# Humi_Light_Pump.net
KiCad netlist of a schematic drawn in Altium Designer
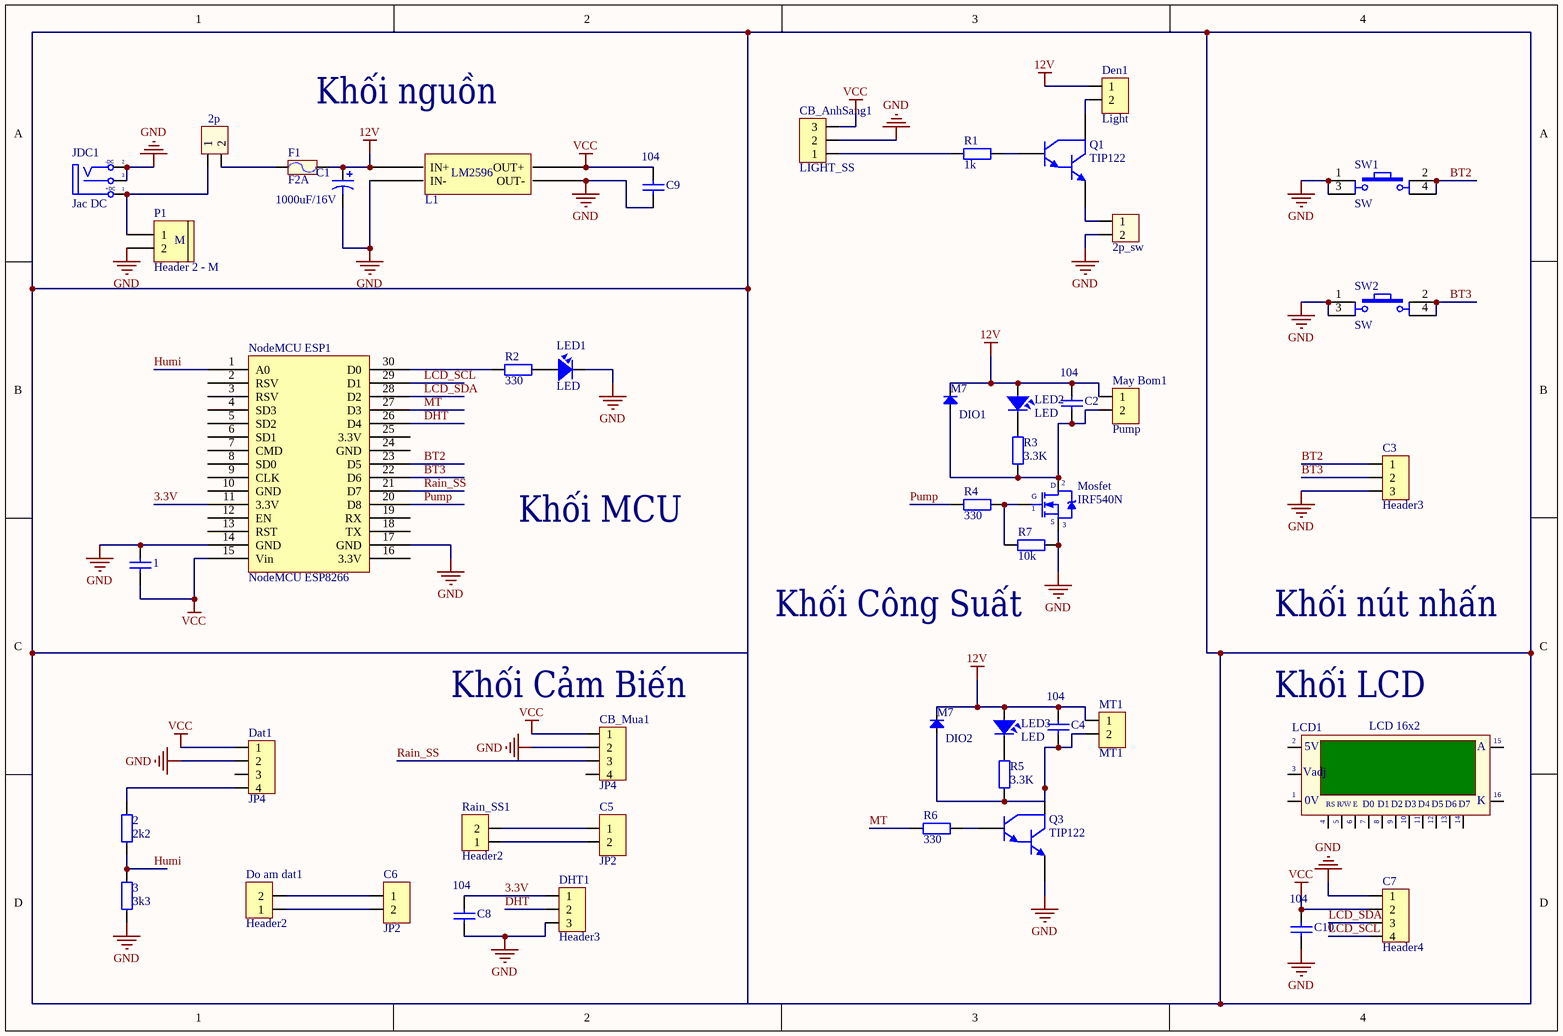
[diagram p0: Humi_Light_Pump.SchDoc]

(export (version "E")
  (design (tool "Eeschema 10.0.6"))
  (components
    (comp (ref "1")
      (value "Capacitor Ceramic")
      (footprint "C1206")
      (description "Capacitor")
      (fields (field (name "PUBLISHER") "Altium Limited"))
      (libsource (lib "My Library") (part "CapSMD"))
    )
    (comp (ref "2")
      (value "2k2")
      (footprint "RES-SMD-1206")
      (description "Resistor SMD 0805")
      (fields (field (name "PUBLISHER") "Altium Limited"))
      (libsource (lib "") (part "R0805_1"))
    )
    (comp (ref "3")
      (value "3k3")
      (footprint "RES-SMD-1206")
      (description "Resistor SMD 0805")
      (fields (field (name "PUBLISHER") "Altium Limited"))
      (libsource (lib "") (part "R0805_1"))
    )
    (comp (ref "C1")
      (value "1000uF/16V")
      (footprint "C8mm")
      (description "Polarized Capacitor (Axial)")
      (fields (field (name "PUBLISHER") "Altium Limited"))
      (libsource (lib "My Library") (part "Cap Pol 12mm"))
    )
    (comp (ref "C2")
      (value "104")
      (footprint "C1206")
      (description "Capacitor")
      (fields (field (name "PUBLISHER") "Altium Limited"))
      (libsource (lib "My Library") (part "CapSMD"))
    )
    (comp (ref "C3")
      (value "Header3")
      (footprint "Header3")
      (description "Header IDC, 3 x 1 Pin Vertical 2.54mm Pitch (Non-Boxed, Male)")
      (fields
        (field (name "MANUFACTURER") "Würth Elektronik eiSos GmbH")
        (field (name "PARTNO") "613002143121")
        (field (name "CREATED BY") "Karrer Zheng")
      )
      (libsource (lib "My Library") (part "Header3"))
    )
    (comp (ref "C4")
      (value "104")
      (footprint "C1206")
      (description "Capacitor")
      (fields (field (name "PUBLISHER") "Altium Limited"))
      (libsource (lib "My Library") (part "CapSMD"))
    )
    (comp (ref "C5")
      (value "JP2")
      (footprint "Header 2P DC 2.54")
      (description "WR-PHD 2.54 mm Angled Socket Header")
      (fields
        (field (name "MANUFACTURER") "Würth Elektronik eiSos GmbH")
        (field (name "PARTNO") "613002143121")
        (field (name "CREATED BY") "Karrer Zheng")
      )
      (libsource (lib "My Library") (part "JP2"))
    )
    (comp (ref "C6")
      (value "JP2")
      (footprint "Header 2P DC 2.54")
      (description "WR-PHD 2.54 mm Angled Socket Header")
      (fields
        (field (name "MANUFACTURER") "Würth Elektronik eiSos GmbH")
        (field (name "PARTNO") "613002143121")
        (field (name "CREATED BY") "Karrer Zheng")
      )
      (libsource (lib "My Library") (part "JP2"))
    )
    (comp (ref "C7")
      (value "Header4")
      (footprint "XH2.54M-4")
      (description "Header IDC, 4 x 1 Pin Vertical 2.54mm Pitch (Non-Boxed, Male)")
      (fields
        (field (name "MANUFACTURER") "Würth Elektronik eiSos GmbH")
        (field (name "PARTNO") "613002143121")
        (field (name "CREATED BY") "Karrer Zheng")
      )
      (libsource (lib "My Library") (part "Header4"))
    )
    (comp (ref "C8")
      (value "104")
      (footprint "C1206")
      (description "Capacitor")
      (fields (field (name "PUBLISHER") "Altium Limited"))
      (libsource (lib "My Library") (part "CapSMD"))
    )
    (comp (ref "C9")
      (value "104")
      (footprint "C1206")
      (description "Capacitor")
      (fields (field (name "PUBLISHER") "Altium Limited"))
      (libsource (lib "My Library") (part "CapSMD"))
    )
    (comp (ref "C10")
      (value "104")
      (footprint "C1206")
      (description "Capacitor")
      (fields (field (name "PUBLISHER") "Altium Limited"))
      (libsource (lib "My Library") (part "CapSMD"))
    )
    (comp (ref "CB_AnhSang1")
      (value "LIGHT_SS")
      (footprint "Header 3P DC 2.54")
      (description "Header IDC, 3 x 1 Pin Vertical 2.54mm Pitch (Non-Boxed, Male)")
      (fields
        (field (name "MANUFACTURER") "Würth Elektronik eiSos GmbH")
        (field (name "PARTNO") "613002143121")
        (field (name "CREATED BY") "Karrer Zheng")
      )
      (libsource (lib "") (part "Header3_1"))
    )
    (comp (ref "CB_Mua1")
      (value "JP4")
      (footprint "JP4-C1T")
      (description "Header IDC, 4 x 1 Pin Vertical 2.54mm Pitch (Non-Boxed, Male)")
      (fields
        (field (name "MANUFACTURER") "Würth Elektronik eiSos GmbH")
        (field (name "PARTNO") "613002143121")
        (field (name "CREATED BY") "Karrer Zheng")
      )
      (libsource (lib "My Library") (part "Header4"))
    )
    (comp (ref "Dat1")
      (value "JP4")
      (footprint "JP4-C1T")
      (description "Header IDC, 4 x 1 Pin Vertical 2.54mm Pitch (Non-Boxed, Male)")
      (fields
        (field (name "MANUFACTURER") "Würth Elektronik eiSos GmbH")
        (field (name "PARTNO") "613002143121")
        (field (name "CREATED BY") "Karrer Zheng")
      )
      (libsource (lib "My Library") (part "Header4"))
    )
    (comp (ref "Den1")
      (value "Light")
      (footprint "Header 2P DC 2.54")
      (description "Header IDC, 2 x 1 Pin Vertical 2.54mm Pitch (Non-Boxed, Male)")
      (fields
        (field (name "MANUFACTURER") "Würth Elektronik eiSos GmbH")
        (field (name "PARTNO") "613002143121")
        (field (name "CREATED BY") "Karrer Zheng")
      )
      (libsource (lib "My Library") (part "Header2"))
    )
    (comp (ref "DHT1")
      (value "Header3")
      (footprint "Header 3P DC 2.54")
      (description "Header IDC, 3 x 1 Pin Vertical 2.54mm Pitch (Non-Boxed, Male)")
      (fields
        (field (name "MANUFACTURER") "Würth Elektronik eiSos GmbH")
        (field (name "PARTNO") "613002143121")
        (field (name "CREATED BY") "Karrer Zheng")
      )
      (libsource (lib "My Library") (part "Header3"))
    )
    (comp (ref "DIO1")
      (value "M7")
      (footprint "DIO-SMD-106")
      (description "Default Diode")
      (fields (field (name "PUBLISHER") "Altium Limited"))
      (libsource (lib "My Library (1)") (part "Diode SMD"))
    )
    (comp (ref "DIO2")
      (value "M7")
      (footprint "DIO-SMD-106")
      (description "Default Diode")
      (fields (field (name "PUBLISHER") "Altium Limited"))
      (libsource (lib "My Library (1)") (part "Diode SMD"))
    )
    (comp (ref "Do am dat1")
      (value "Header2")
      (footprint "Header2")
      (description "Header IDC, 2 x 1 Pin Vertical 2.54mm Pitch (Non-Boxed, Male)")
      (fields
        (field (name "MANUFACTURER") "Würth Elektronik eiSos GmbH")
        (field (name "PARTNO") "613002143121")
        (field (name "CREATED BY") "Karrer Zheng")
      )
      (libsource (lib "") (part "Header2_1"))
    )
    (comp (ref "F1")
      (value "F2A")
      (footprint "Fuse")
      (description "Fuse")
      (fields (field (name "DESIGNED BY") "VanDungEvn"))
      (libsource (lib "My Library") (part "Fuse"))
    )
    (comp (ref "H1")
      (value "2p")
      (footprint "XH2.54M-2")
      (description "Cắm")
      (libsource (lib "") (part "Header 2P 2.54 Duc Thang_1"))
    )
    (comp (ref "H2")
      (value "2p_sw")
      (footprint "XH2.54M-2")
      (description "Cắm")
      (libsource (lib "Header") (part "Header 2P 2.54 Duc Thang"))
    )
    (comp (ref "JDC1")
      (value "Jac DC")
      (footprint "DC-IN")
      (description "Jac DC input")
      (libsource (lib "My Library") (part "DCIN"))
    )
    (comp (ref "L1")
      (value "BUCK_LM2596")
      (footprint "BUCK_LM2596")
      (libsource (lib "BUCK_LM2596_Sch") (part "BUCK_LM2596"))
    )
    (comp (ref "LCD1")
      (value "LCD 16x2")
      (footprint "LCD16X2N")
      (libsource (lib "My library altium") (part "LCD"))
    )
    (comp (ref "LED1")
      (value "LED")
      (footprint "LED-5 GRe")
      (description "LED Single colour Green and Red")
      (libsource (lib "My Library") (part "LED"))
    )
    (comp (ref "LED2")
      (value "LED")
      (footprint "LED-5 GRe")
      (description "LED Single colour Green and Red")
      (libsource (lib "My Library") (part "LED"))
    )
    (comp (ref "LED3")
      (value "LED")
      (footprint "LED-5 GRe")
      (description "LED Single colour Green and Red")
      (libsource (lib "My Library") (part "LED"))
    )
    (comp (ref "May Bom1")
      (value "Pump")
      (footprint "Header 2P DC 2.54")
      (description "Header IDC, 2 x 1 Pin Vertical 2.54mm Pitch (Non-Boxed, Male)")
      (fields
        (field (name "MANUFACTURER") "Würth Elektronik eiSos GmbH")
        (field (name "PARTNO") "613002143121")
        (field (name "CREATED BY") "Karrer Zheng")
      )
      (libsource (lib "My Library") (part "Header2"))
    )
    (comp (ref "Mosfet")
      (value "IRF540N")
      (footprint "QTO-220")
      (description "MOSFET N - CHANNEL 500V - 0.75 - 8A - TO-220")
      (libsource (lib "My Library") (part "IRF840"))
    )
    (comp (ref "MT1")
      (value "MT1")
      (footprint "Header 2P DC 2.54")
      (description "Header IDC, 2 x 1 Pin Vertical 2.54mm Pitch (Non-Boxed, Male)")
      (fields
        (field (name "MANUFACTURER") "Würth Elektronik eiSos GmbH")
        (field (name "PARTNO") "613002143121")
        (field (name "CREATED BY") "Karrer Zheng")
      )
      (libsource (lib "My Library") (part "Header2"))
    )
    (comp (ref "NodeMCU ESP1")
      (value "NodeMCU ESP8266")
      (footprint "NodeMCU ESP8266")
      (libsource (lib "Phieu_Du") (part "NodeMCU ESP8266"))
    )
    (comp (ref "P1")
      (value "Header 2 - M")
      (footprint "Medium - Header 2")
      (description "Header, 2-Pin, Medium")
      (fields (field (name "PUBLISHER") "Altium Limited"))
      (libsource (lib "My Library") (part "Header 2 - M"))
    )
    (comp (ref "Q1")
      (value "TIP122")
      (footprint "QTO-220")
      (description "Darlington Silicon Power NPN Transistor, 8 Amp, 100 Volts and 65 Watts")
      (libsource (lib "My Library (1)") (part "TIP122"))
    )
    (comp (ref "Q3")
      (value "TIP122")
      (footprint "QTO-220")
      (description "Darlington Silicon Power NPN Transistor, 8 Amp, 100 Volts and 65 Watts")
      (libsource (lib "My Library (1)") (part "TIP122"))
    )
    (comp (ref "R1")
      (value "1k")
      (footprint "RES-SMD-1206")
      (description "Resistor SMD 0805")
      (fields (field (name "PUBLISHER") "Altium Limited"))
      (libsource (lib "My Library (1)") (part "R0805"))
    )
    (comp (ref "R2")
      (value "330")
      (footprint "RES-SMD-1206")
      (description "Resistor SMD 0805")
      (fields (field (name "PUBLISHER") "Altium Limited"))
      (libsource (lib "My Library (1)") (part "R0805"))
    )
    (comp (ref "R3")
      (value "3.3K")
      (footprint "RES-SMD-1206")
      (description "Resistor SMD 0805")
      (fields (field (name "PUBLISHER") "Altium Limited"))
      (libsource (lib "") (part "R0805_1"))
    )
    (comp (ref "R4")
      (value "330")
      (footprint "RES-SMD-1206")
      (description "Resistor SMD 0805")
      (fields (field (name "PUBLISHER") "Altium Limited"))
      (libsource (lib "My Library (1)") (part "R0805"))
    )
    (comp (ref "R5")
      (value "3.3K")
      (footprint "RES-SMD-1206")
      (description "Resistor SMD 0805")
      (fields (field (name "PUBLISHER") "Altium Limited"))
      (libsource (lib "") (part "R0805_1"))
    )
    (comp (ref "R6")
      (value "330")
      (footprint "RES-SMD-1206")
      (description "Resistor SMD 0805")
      (fields (field (name "PUBLISHER") "Altium Limited"))
      (libsource (lib "My Library (1)") (part "R0805"))
    )
    (comp (ref "R7")
      (value "10k")
      (footprint "RES-SMD-1206")
      (description "Resistor SMD 0805")
      (fields (field (name "PUBLISHER") "Altium Limited"))
      (libsource (lib "My Library (1)") (part "R0805"))
    )
    (comp (ref "Rain_SS1")
      (value "Header2")
      (footprint "Header2")
      (description "Header IDC, 2 x 1 Pin Vertical 2.54mm Pitch (Non-Boxed, Male)")
      (fields
        (field (name "MANUFACTURER") "Würth Elektronik eiSos GmbH")
        (field (name "PARTNO") "613002143121")
        (field (name "CREATED BY") "Karrer Zheng")
      )
      (libsource (lib "") (part "Header2_1"))
    )
    (comp (ref "SW1")
      (value "SW")
      (footprint "SW4")
      (description "Switch button 4 pin")
      (libsource (lib "My Library (1)") (part "SW4"))
    )
    (comp (ref "SW2")
      (value "SW")
      (footprint "SW4")
      (description "Switch button 4 pin")
      (libsource (lib "My Library (1)") (part "SW4"))
    )
  )
  (nets
    (net (code "1") (name "/3.3V") (class "Default")
      (node (ref "C8") (pin "2") (pinfunction "2_2") (pintype "passive"))
      (node (ref "DHT1") (pin "1") (pinfunction "1_1") (pintype "passive"))
      (node (ref "NodeMCU ESP1") (pin "11") (pinfunction "3.3V_11") (pintype "passive"))
    )
    (net (code "2") (name "/BT2") (class "Default")
      (node (ref "C3") (pin "1") (pinfunction "1_1") (pintype "passive"))
      (node (ref "NodeMCU ESP1") (pin "23") (pinfunction "D5_23") (pintype "passive"))
      (node (ref "SW1") (pin "2") (pintype "passive"))
      (node (ref "SW1") (pin "4") (pintype "passive"))
    )
    (net (code "3") (name "/BT3") (class "Default")
      (node (ref "C3") (pin "2") (pinfunction "2_2") (pintype "passive"))
      (node (ref "NodeMCU ESP1") (pin "22") (pinfunction "D6_22") (pintype "passive"))
      (node (ref "SW2") (pin "2") (pintype "passive"))
      (node (ref "SW2") (pin "4") (pintype "passive"))
    )
    (net (code "4") (name "/DHT") (class "Default")
      (node (ref "DHT1") (pin "2") (pinfunction "2_2") (pintype "passive"))
      (node (ref "NodeMCU ESP1") (pin "26") (pinfunction "D4_26") (pintype "passive"))
    )
    (net (code "5") (name "/Humi") (class "Default")
      (node (ref "2") (pin "2") (pinfunction "2_2") (pintype "passive"))
      (node (ref "3") (pin "1") (pinfunction "1_1") (pintype "passive"))
      (node (ref "NodeMCU ESP1") (pin "1") (pinfunction "A0_1") (pintype "passive"))
    )
    (net (code "6") (name "/LCD_SCL") (class "Default")
      (node (ref "C7") (pin "4") (pinfunction "4_4") (pintype "passive"))
      (node (ref "NodeMCU ESP1") (pin "29") (pinfunction "D1_29") (pintype "passive"))
    )
    (net (code "7") (name "/LCD_SDA") (class "Default")
      (node (ref "C7") (pin "3") (pinfunction "3_3") (pintype "passive"))
      (node (ref "NodeMCU ESP1") (pin "28") (pinfunction "D2_28") (pintype "passive"))
    )
    (net (code "8") (name "/MT") (class "Default")
      (node (ref "NodeMCU ESP1") (pin "27") (pinfunction "D3_27") (pintype "passive"))
      (node (ref "R6") (pin "2") (pinfunction "2_2") (pintype "passive"))
    )
    (net (code "9") (name "/Pump") (class "Default")
      (node (ref "NodeMCU ESP1") (pin "20") (pinfunction "D8_20") (pintype "passive"))
      (node (ref "R4") (pin "2") (pinfunction "2_2") (pintype "passive"))
    )
    (net (code "10") (name "/Rain_SS") (class "Default")
      (node (ref "CB_Mua1") (pin "3") (pinfunction "3_3") (pintype "passive"))
      (node (ref "NodeMCU ESP1") (pin "21") (pinfunction "D7_21") (pintype "passive"))
    )
    (net (code "11") (name "12V") (class "Default")
      (node (ref "C1") (pin "1") (pinfunction "1_1") (pintype "passive"))
      (node (ref "C2") (pin "2") (pinfunction "2_2") (pintype "passive"))
      (node (ref "C4") (pin "2") (pinfunction "2_2") (pintype "passive"))
      (node (ref "DIO1") (pin "2") (pinfunction "K_2") (pintype "passive"))
      (node (ref "DIO2") (pin "2") (pinfunction "K_2") (pintype "passive"))
      (node (ref "Den1") (pin "1") (pinfunction "1_1") (pintype "passive"))
      (node (ref "F1") (pin "2") (pinfunction "2_2") (pintype "passive"))
      (node (ref "L1") (pin "1") (pinfunction "IN+_1") (pintype "passive"))
      (node (ref "LED2") (pin "1") (pinfunction "1_1") (pintype "passive"))
      (node (ref "LED3") (pin "1") (pinfunction "1_1") (pintype "passive"))
      (node (ref "MT1") (pin "1") (pinfunction "1_1") (pintype "passive"))
      (node (ref "May Bom1") (pin "1") (pinfunction "1_1") (pintype "passive"))
    )
    (net (code "12") (name "GND") (class "Default")
      (node (ref "1") (pin "2") (pinfunction "2_2") (pintype "passive"))
      (node (ref "3") (pin "2") (pinfunction "2_2") (pintype "passive"))
      (node (ref "C1") (pin "2") (pinfunction "2_2") (pintype "passive"))
      (node (ref "C10") (pin "1") (pinfunction "1_1") (pintype "passive"))
      (node (ref "C3") (pin "3") (pinfunction "3_3") (pintype "passive"))
      (node (ref "C7") (pin "1") (pinfunction "1_1") (pintype "passive"))
      (node (ref "C8") (pin "1") (pinfunction "1_1") (pintype "passive"))
      (node (ref "C9") (pin "1") (pinfunction "1_1") (pintype "passive"))
      (node (ref "CB_AnhSang1") (pin "2") (pinfunction "2_2") (pintype "passive"))
      (node (ref "CB_Mua1") (pin "2") (pinfunction "2_2") (pintype "passive"))
      (node (ref "DHT1") (pin "3") (pinfunction "3_3") (pintype "passive"))
      (node (ref "Dat1") (pin "2") (pinfunction "2_2") (pintype "passive"))
      (node (ref "H2") (pin "2") (pinfunction "2_2") (pintype "passive"))
      (node (ref "JDC1") (pin "2") (pinfunction "TN_2") (pintype "passive"))
      (node (ref "JDC1") (pin "3") (pinfunction "S_3") (pintype "power_in"))
      (node (ref "L1") (pin "2") (pinfunction "IN-_2") (pintype "passive"))
      (node (ref "L1") (pin "3") (pinfunction "OUT-_3") (pintype "passive"))
      (node (ref "LED1") (pin "2") (pinfunction "2_2") (pintype "passive"))
      (node (ref "Mosfet") (pin "3") (pinfunction "S_3") (pintype "passive"))
      (node (ref "NodeMCU ESP1") (pin "14") (pinfunction "GND_14") (pintype "passive"))
      (node (ref "NodeMCU ESP1") (pin "17") (pinfunction "GND_17") (pintype "passive"))
      (node (ref "P1") (pin "2") (pinfunction "2_2") (pintype "passive"))
      (node (ref "Q3") (pin "3") (pinfunction "E_3") (pintype "passive"))
      (node (ref "R7") (pin "1") (pinfunction "1_1") (pintype "passive"))
      (node (ref "SW1") (pin "1") (pintype "passive"))
      (node (ref "SW1") (pin "3") (pintype "passive"))
      (node (ref "SW2") (pin "1") (pintype "passive"))
      (node (ref "SW2") (pin "3") (pintype "passive"))
    )
    (net (code "13") (name "Net-(2-Pad1)") (class "Default")
      (node (ref "2") (pin "1") (pinfunction "1_1") (pintype "passive"))
      (node (ref "Dat1") (pin "4") (pinfunction "4_4") (pintype "passive"))
    )
    (net (code "14") (name "Net-(C5-Pad1)") (class "Default")
      (node (ref "C5") (pin "1") (pinfunction "1_1") (pintype "passive"))
      (node (ref "Rain_SS1") (pin "2") (pinfunction "2_2") (pintype "passive"))
    )
    (net (code "15") (name "Net-(C5-Pad2)") (class "Default")
      (node (ref "C5") (pin "2") (pinfunction "2_2") (pintype "passive"))
      (node (ref "Rain_SS1") (pin "1") (pinfunction "1_1") (pintype "passive"))
    )
    (net (code "16") (name "Net-(C6-Pad1)") (class "Default")
      (node (ref "C6") (pin "1") (pinfunction "1_1") (pintype "passive"))
      (node (ref "Do am dat1") (pin "2") (pinfunction "2_2") (pintype "passive"))
    )
    (net (code "17") (name "Net-(C6-Pad2)") (class "Default")
      (node (ref "C6") (pin "2") (pinfunction "2_2") (pintype "passive"))
      (node (ref "Do am dat1") (pin "1") (pinfunction "1_1") (pintype "passive"))
    )
    (net (code "18") (name "Net-(CB_AnhSang1-Pad1)") (class "Default")
      (node (ref "CB_AnhSang1") (pin "1") (pinfunction "1_1") (pintype "passive"))
      (node (ref "R1") (pin "2") (pinfunction "2_2") (pintype "passive"))
    )
    (net (code "19") (name "Net-(DIO1-A)") (class "Default")
      (node (ref "C2") (pin "1") (pinfunction "1_1") (pintype "passive"))
      (node (ref "DIO1") (pin "1") (pinfunction "A_1") (pintype "passive"))
      (node (ref "May Bom1") (pin "2") (pinfunction "2_2") (pintype "passive"))
      (node (ref "Mosfet") (pin "2") (pinfunction "D_2") (pintype "passive"))
      (node (ref "R3") (pin "2") (pinfunction "2_2") (pintype "passive"))
    )
    (net (code "20") (name "Net-(DIO2-A)") (class "Default")
      (node (ref "C4") (pin "1") (pinfunction "1_1") (pintype "passive"))
      (node (ref "DIO2") (pin "1") (pinfunction "A_1") (pintype "passive"))
      (node (ref "MT1") (pin "2") (pinfunction "2_2") (pintype "passive"))
      (node (ref "Q3") (pin "2") (pinfunction "C_2") (pintype "passive"))
      (node (ref "R5") (pin "2") (pinfunction "2_2") (pintype "passive"))
    )
    (net (code "21") (name "Net-(F1-Pad1)") (class "Default")
      (node (ref "F1") (pin "1") (pinfunction "1_1") (pintype "passive"))
      (node (ref "H1") (pin "2") (pinfunction "2_2") (pintype "passive"))
    )
    (net (code "22") (name "Net-(JDC1-T)") (class "Default")
      (node (ref "H1") (pin "1") (pinfunction "1_1") (pintype "passive"))
      (node (ref "JDC1") (pin "1") (pinfunction "T_1") (pintype "passive"))
      (node (ref "P1") (pin "1") (pinfunction "1_1") (pintype "passive"))
    )
    (net (code "23") (name "Net-(LED1-Pad1)") (class "Default")
      (node (ref "LED1") (pin "1") (pinfunction "1_1") (pintype "passive"))
      (node (ref "R2") (pin "1") (pinfunction "1_1") (pintype "passive"))
    )
    (net (code "24") (name "Net-(LED2-Pad2)") (class "Default")
      (node (ref "LED2") (pin "2") (pinfunction "2_2") (pintype "passive"))
      (node (ref "R3") (pin "1") (pinfunction "1_1") (pintype "passive"))
    )
    (net (code "25") (name "Net-(LED3-Pad2)") (class "Default")
      (node (ref "LED3") (pin "2") (pinfunction "2_2") (pintype "passive"))
      (node (ref "R5") (pin "1") (pinfunction "1_1") (pintype "passive"))
    )
    (net (code "26") (name "Net-(Mosfet-G)") (class "Default")
      (node (ref "Mosfet") (pin "1") (pinfunction "G_1") (pintype "passive"))
      (node (ref "R4") (pin "1") (pinfunction "1_1") (pintype "passive"))
      (node (ref "R7") (pin "2") (pinfunction "2_2") (pintype "passive"))
    )
    (net (code "27") (name "Net-(NodeMCU ESP1-D0)") (class "Default")
      (node (ref "NodeMCU ESP1") (pin "30") (pinfunction "D0_30") (pintype "passive"))
      (node (ref "R2") (pin "2") (pinfunction "2_2") (pintype "passive"))
    )
    (net (code "28") (name "Net-(Q1-B)") (class "Default")
      (node (ref "Q1") (pin "1") (pinfunction "B_1") (pintype "passive"))
      (node (ref "R1") (pin "1") (pinfunction "1_1") (pintype "passive"))
    )
    (net (code "29") (name "Net-(Q1-C)") (class "Default")
      (node (ref "Den1") (pin "2") (pinfunction "2_2") (pintype "passive"))
      (node (ref "Q1") (pin "2") (pinfunction "C_2") (pintype "passive"))
    )
    (net (code "30") (name "Net-(Q1-E)") (class "Default")
      (node (ref "H2") (pin "1") (pinfunction "1_1") (pintype "passive"))
      (node (ref "Q1") (pin "3") (pinfunction "E_3") (pintype "passive"))
    )
    (net (code "31") (name "Net-(Q3-B)") (class "Default")
      (node (ref "Q3") (pin "1") (pinfunction "B_1") (pintype "passive"))
      (node (ref "R6") (pin "1") (pinfunction "1_1") (pintype "passive"))
    )
    (net (code "32") (name "VCC") (class "Default")
      (node (ref "1") (pin "1") (pinfunction "1_1") (pintype "passive"))
      (node (ref "C10") (pin "2") (pinfunction "2_2") (pintype "passive"))
      (node (ref "C7") (pin "2") (pinfunction "2_2") (pintype "passive"))
      (node (ref "C9") (pin "2") (pinfunction "2_2") (pintype "passive"))
      (node (ref "CB_AnhSang1") (pin "3") (pinfunction "3_3") (pintype "passive"))
      (node (ref "CB_Mua1") (pin "1") (pinfunction "1_1") (pintype "passive"))
      (node (ref "Dat1") (pin "1") (pinfunction "1_1") (pintype "passive"))
      (node (ref "L1") (pin "4") (pinfunction "OUT+_4") (pintype "passive"))
      (node (ref "NodeMCU ESP1") (pin "15") (pinfunction "Vin_15") (pintype "passive"))
    )
    (net (code "33") (name "unconnected-(CB_Mua1-Pad4)") (class "Default")
      (node (ref "CB_Mua1") (pin "4") (pinfunction "4_4") (pintype "passive"))
    )
    (net (code "34") (name "unconnected-(Dat1-Pad3)") (class "Default")
      (node (ref "Dat1") (pin "3") (pinfunction "3_3") (pintype "passive"))
    )
    (net (code "35") (name "unconnected-(LCD1-A-Pad15)") (class "Default")
      (node (ref "LCD1") (pin "15") (pinfunction "A_15") (pintype "passive"))
    )
    (net (code "36") (name "unconnected-(LCD1-D0-Pad7)") (class "Default")
      (node (ref "LCD1") (pin "7") (pinfunction "D0_7") (pintype "passive"))
    )
    (net (code "37") (name "unconnected-(LCD1-D1-Pad8)") (class "Default")
      (node (ref "LCD1") (pin "8") (pinfunction "D1_8") (pintype "passive"))
    )
    (net (code "38") (name "unconnected-(LCD1-D2-Pad9)") (class "Default")
      (node (ref "LCD1") (pin "9") (pinfunction "D2_9") (pintype "passive"))
    )
    (net (code "39") (name "unconnected-(LCD1-D3-Pad10)") (class "Default")
      (node (ref "LCD1") (pin "10") (pinfunction "D3_10") (pintype "passive"))
    )
    (net (code "40") (name "unconnected-(LCD1-D4-Pad11)") (class "Default")
      (node (ref "LCD1") (pin "11") (pinfunction "D4_11") (pintype "passive"))
    )
    (net (code "41") (name "unconnected-(LCD1-D5-Pad12)") (class "Default")
      (node (ref "LCD1") (pin "12") (pinfunction "D5_12") (pintype "passive"))
    )
    (net (code "42") (name "unconnected-(LCD1-D6-Pad13)") (class "Default")
      (node (ref "LCD1") (pin "13") (pinfunction "D6_13") (pintype "passive"))
    )
    (net (code "43") (name "unconnected-(LCD1-D7-Pad14)") (class "Default")
      (node (ref "LCD1") (pin "14") (pinfunction "D7_14") (pintype "passive"))
    )
    (net (code "44") (name "unconnected-(LCD1-GND-Pad1)") (class "Default")
      (node (ref "LCD1") (pin "1") (pinfunction "GND_1") (pintype "passive"))
    )
    (net (code "45") (name "unconnected-(LCD1-K-Pad16)") (class "Default")
      (node (ref "LCD1") (pin "16") (pinfunction "K_16") (pintype "passive"))
    )
    (net (code "46") (name "unconnected-(LCD1-RS-Pad4)") (class "Default")
      (node (ref "LCD1") (pin "4") (pinfunction "RS_4") (pintype "passive"))
    )
    (net (code "47") (name "unconnected-(LCD1-R{slash}~{W}-Pad5)") (class "Default")
      (node (ref "LCD1") (pin "5") (pinfunction "R/~{W}_5") (pintype "passive"))
    )
    (net (code "48") (name "unconnected-(LCD1-VAdj-Pad3)") (class "Default")
      (node (ref "LCD1") (pin "3") (pinfunction "VAdj_3") (pintype "passive"))
    )
    (net (code "49") (name "unconnected-(LCD1-VDD-Pad2)") (class "Default")
      (node (ref "LCD1") (pin "2") (pinfunction "VDD_2") (pintype "passive"))
    )
    (net (code "50") (name "unconnected-(LCD1-~{EN}-Pad6)") (class "Default")
      (node (ref "LCD1") (pin "6") (pinfunction "~{EN}_6") (pintype "passive"))
    )
    (net (code "51") (name "unconnected-(NodeMCU ESP1-3.3V-Pad16)") (class "Default")
      (node (ref "NodeMCU ESP1") (pin "16") (pinfunction "3.3V_16") (pintype "passive"))
    )
    (net (code "52") (name "unconnected-(NodeMCU ESP1-3.3V-Pad25)") (class "Default")
      (node (ref "NodeMCU ESP1") (pin "25") (pinfunction "3.3V_25") (pintype "passive"))
    )
    (net (code "53") (name "unconnected-(NodeMCU ESP1-CLK-Pad9)") (class "Default")
      (node (ref "NodeMCU ESP1") (pin "9") (pinfunction "CLK_9") (pintype "passive"))
    )
    (net (code "54") (name "unconnected-(NodeMCU ESP1-CMD-Pad7)") (class "Default")
      (node (ref "NodeMCU ESP1") (pin "7") (pinfunction "CMD_7") (pintype "passive"))
    )
    (net (code "55") (name "unconnected-(NodeMCU ESP1-EN-Pad12)") (class "Default")
      (node (ref "NodeMCU ESP1") (pin "12") (pinfunction "EN_12") (pintype "passive"))
    )
    (net (code "56") (name "unconnected-(NodeMCU ESP1-GND-Pad10)") (class "Default")
      (node (ref "NodeMCU ESP1") (pin "10") (pinfunction "GND_10") (pintype "passive"))
    )
    (net (code "57") (name "unconnected-(NodeMCU ESP1-GND-Pad24)") (class "Default")
      (node (ref "NodeMCU ESP1") (pin "24") (pinfunction "GND_24") (pintype "passive"))
    )
    (net (code "58") (name "unconnected-(NodeMCU ESP1-RST-Pad13)") (class "Default")
      (node (ref "NodeMCU ESP1") (pin "13") (pinfunction "RST_13") (pintype "passive"))
    )
    (net (code "59") (name "unconnected-(NodeMCU ESP1-RSV-Pad2)") (class "Default")
      (node (ref "NodeMCU ESP1") (pin "2") (pinfunction "RSV_2") (pintype "passive"))
    )
    (net (code "60") (name "unconnected-(NodeMCU ESP1-RSV-Pad3)") (class "Default")
      (node (ref "NodeMCU ESP1") (pin "3") (pinfunction "RSV_3") (pintype "passive"))
    )
    (net (code "61") (name "unconnected-(NodeMCU ESP1-RX-Pad19)") (class "Default")
      (node (ref "NodeMCU ESP1") (pin "19") (pinfunction "RX_19") (pintype "passive"))
    )
    (net (code "62") (name "unconnected-(NodeMCU ESP1-SD0-Pad8)") (class "Default")
      (node (ref "NodeMCU ESP1") (pin "8") (pinfunction "SD0_8") (pintype "passive"))
    )
    (net (code "63") (name "unconnected-(NodeMCU ESP1-SD1-Pad6)") (class "Default")
      (node (ref "NodeMCU ESP1") (pin "6") (pinfunction "SD1_6") (pintype "passive"))
    )
    (net (code "64") (name "unconnected-(NodeMCU ESP1-SD2-Pad5)") (class "Default")
      (node (ref "NodeMCU ESP1") (pin "5") (pinfunction "SD2_5") (pintype "passive"))
    )
    (net (code "65") (name "unconnected-(NodeMCU ESP1-SD3-Pad4)") (class "Default")
      (node (ref "NodeMCU ESP1") (pin "4") (pinfunction "SD3_4") (pintype "passive"))
    )
    (net (code "66") (name "unconnected-(NodeMCU ESP1-TX-Pad18)") (class "Default")
      (node (ref "NodeMCU ESP1") (pin "18") (pinfunction "TX_18") (pintype "passive"))
    )
  )
)
